# partybooth.net
KiCad netlist of a schematic drawn in EAGLE
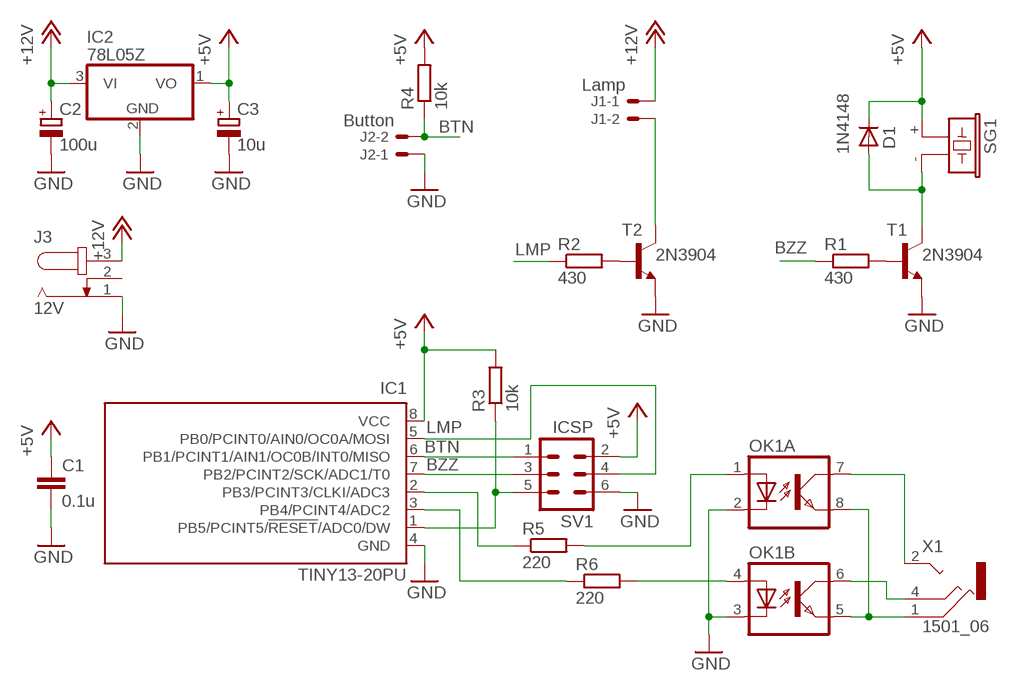
[diagram p0: schematic, sheet 1]

(export (version "E")
  (design (tool "Eeschema 10.0.6"))
  (components
    (comp (ref "C1")
      (value "0.1u")
      (footprint "eagle-import:C050-025X075")
      (libsource (lib "eagle-import") (part "C-EU050-025X075"))
    )
    (comp (ref "C2")
      (value "100u")
      (footprint "eagle-import:B45181B")
      (libsource (lib "eagle-import") (part "CPOL-EUB45181B"))
    )
    (comp (ref "C3")
      (value "10u")
      (footprint "eagle-import:B45181B")
      (libsource (lib "eagle-import") (part "CPOL-EUB45181B"))
    )
    (comp (ref "D1")
      (value "1N4148")
      (footprint "eagle-import:DO35-7")
      (libsource (lib "eagle-import") (part "1N4148DO35-7"))
    )
    (comp (ref "IC1")
      (value "TINY13-20PU")
      (footprint "eagle-import:DIL08")
      (fields (field (name "MPN") "ATTINY13-20PU"))
      (libsource (lib "eagle-import") (part "TINY13PU-20"))
    )
    (comp (ref "IC2")
      (value "78L05Z")
      (footprint "eagle-import:TO92")
      (libsource (lib "eagle-import") (part "78ZL05"))
    )
    (comp (ref "J1")
      (value "Lamp")
      (footprint "eagle-import:6410-02")
      (libsource (lib "eagle-import") (part "22-?-0227-2021"))
    )
    (comp (ref "J2")
      (value "Button")
      (footprint "eagle-import:6410-02")
      (libsource (lib "eagle-import") (part "22-?-0227-2021"))
    )
    (comp (ref "J3")
      (value "12V")
      (footprint "eagle-import:SPC4077")
      (libsource (lib "eagle-import") (part "JACK-PLUG0"))
    )
    (comp (ref "OK1")
      (value "ILD2")
      (footprint "eagle-import:DIL08")
      (libsource (lib "eagle-import") (part "ILD2"))
    )
    (comp (ref "R1")
      (value "430")
      (footprint "eagle-import:0204_7")
      (libsource (lib "eagle-import") (part "R-EU_0204/7"))
    )
    (comp (ref "R2")
      (value "430")
      (footprint "eagle-import:0204_7")
      (libsource (lib "eagle-import") (part "R-EU_0204/7"))
    )
    (comp (ref "R3")
      (value "10k")
      (footprint "eagle-import:0204_7")
      (libsource (lib "eagle-import") (part "R-EU_0204/7"))
    )
    (comp (ref "R4")
      (value "10k")
      (footprint "eagle-import:0204_7")
      (libsource (lib "eagle-import") (part "R-EU_0204/7"))
    )
    (comp (ref "R5")
      (value "220")
      (footprint "eagle-import:0204_7")
      (libsource (lib "eagle-import") (part "R-EU_0204/7"))
    )
    (comp (ref "R6")
      (value "220")
      (footprint "eagle-import:0204_7")
      (libsource (lib "eagle-import") (part "R-EU_0204/7"))
    )
    (comp (ref "SG1")
      (value "F/CM12P")
      (footprint "eagle-import:F_CM12P")
      (libsource (lib "eagle-import") (part "F/CM12P"))
    )
    (comp (ref "SV1")
      (value "ICSP")
      (footprint "eagle-import:MA03-2")
      (libsource (lib "eagle-import") (part "MA03-2"))
    )
    (comp (ref "T1")
      (value "2N3904")
      (footprint "eagle-import:TO92")
      (libsource (lib "eagle-import") (part "2N3904"))
    )
    (comp (ref "T2")
      (value "2N3904")
      (footprint "eagle-import:TO92")
      (libsource (lib "eagle-import") (part "2N3904"))
    )
    (comp (ref "X1")
      (value "1501_06")
      (footprint "eagle-import:1501_06")
      (libsource (lib "eagle-import") (part "1501_06"))
    )
  )
  (nets
    (net (code "1") (name "+5V") (class "Default")
      (node (ref "C1") (pin "1") (pinfunction "1_1") (pintype "passive"))
      (node (ref "C3") (pin "+") (pinfunction "+_+") (pintype "passive"))
      (node (ref "D1") (pin "C") (pinfunction "C_C") (pintype "passive"))
      (node (ref "IC1") (pin "8") (pinfunction "VCC_8") (pintype "power_in"))
      (node (ref "IC2") (pin "1") (pinfunction "VO_1") (pintype "passive"))
      (node (ref "R3") (pin "2") (pinfunction "2_2") (pintype "passive"))
      (node (ref "R4") (pin "2") (pinfunction "2_2") (pintype "passive"))
      (node (ref "SG1") (pin "+") (pinfunction "1_+") (pintype "passive"))
      (node (ref "SV1") (pin "2") (pinfunction "2_2") (pintype "passive"))
    )
    (net (code "2") (name "+12V") (class "Default")
      (node (ref "C2") (pin "+") (pinfunction "+_+") (pintype "passive"))
      (node (ref "IC2") (pin "3") (pinfunction "VI_3") (pintype "input"))
      (node (ref "J1") (pin "1") (pinfunction "S_1") (pintype "passive"))
      (node (ref "J3") (pin "3") (pinfunction "3_3") (pintype "passive"))
    )
    (net (code "3") (name "/BTN") (class "Default")
      (node (ref "IC1") (pin "6") (pinfunction "PB1/PCINT1/AIN1/OC0B/INT0/MISO_6") (pintype "bidirectional"))
      (node (ref "J2") (pin "2") (pinfunction "S_2") (pintype "passive"))
      (node (ref "R4") (pin "1") (pinfunction "1_1") (pintype "passive"))
      (node (ref "SV1") (pin "1") (pinfunction "1_1") (pintype "passive"))
    )
    (net (code "4") (name "/BZZ") (class "Default")
      (node (ref "IC1") (pin "7") (pinfunction "PB2/PCINT2/SCK/ADC1/T0_7") (pintype "bidirectional"))
      (node (ref "R1") (pin "1") (pinfunction "1_1") (pintype "passive"))
      (node (ref "SV1") (pin "3") (pinfunction "3_3") (pintype "passive"))
    )
    (net (code "5") (name "/LMP") (class "Default")
      (node (ref "IC1") (pin "5") (pinfunction "PB0/PCINT0/AIN0/OC0A/MOSI_5") (pintype "bidirectional"))
      (node (ref "R2") (pin "1") (pinfunction "1_1") (pintype "passive"))
      (node (ref "SV1") (pin "4") (pinfunction "4_4") (pintype "passive"))
    )
    (net (code "6") (name "GND") (class "Default")
      (node (ref "C1") (pin "2") (pinfunction "2_2") (pintype "passive"))
      (node (ref "C2") (pin "-") (pinfunction "-_-") (pintype "passive"))
      (node (ref "C3") (pin "-") (pinfunction "-_-") (pintype "passive"))
      (node (ref "IC1") (pin "4") (pinfunction "GND_4") (pintype "power_in"))
      (node (ref "IC2") (pin "2") (pinfunction "GND_2") (pintype "passive"))
      (node (ref "J2") (pin "1") (pinfunction "S_1") (pintype "passive"))
      (node (ref "J3") (pin "1") (pinfunction "1_1") (pintype "passive"))
      (node (ref "OK1") (pin "2") (pinfunction "C_2") (pintype "passive"))
      (node (ref "OK1") (pin "3") (pinfunction "C_3") (pintype "passive"))
      (node (ref "SV1") (pin "6") (pinfunction "6_6") (pintype "passive"))
      (node (ref "T1") (pin "3") (pinfunction "E_3") (pintype "passive"))
      (node (ref "T2") (pin "3") (pinfunction "E_3") (pintype "passive"))
    )
    (net (code "7") (name "Net-(IC1-PB3{slash}PCINT3{slash}CLKI{slash}ADC3)") (class "Default")
      (node (ref "IC1") (pin "2") (pinfunction "PB3/PCINT3/CLKI/ADC3_2") (pintype "bidirectional"))
      (node (ref "R5") (pin "1") (pinfunction "1_1") (pintype "passive"))
    )
    (net (code "8") (name "Net-(IC1-PB4{slash}PCINT4{slash}ADC2)") (class "Default")
      (node (ref "IC1") (pin "3") (pinfunction "PB4/PCINT4/ADC2_3") (pintype "bidirectional"))
      (node (ref "R6") (pin "1") (pinfunction "1_1") (pintype "passive"))
    )
    (net (code "9") (name "Net-(IC1-PB5{slash}PCINT5{slash}~{RESET}{slash}ADC0{slash}DW)") (class "Default")
      (node (ref "IC1") (pin "1") (pinfunction "PB5/PCINT5/~{RESET}/ADC0/DW_1") (pintype "bidirectional"))
      (node (ref "R3") (pin "1") (pinfunction "1_1") (pintype "passive"))
      (node (ref "SV1") (pin "5") (pinfunction "5_5") (pintype "passive"))
    )
    (net (code "10") (name "Net-(J1B-S)") (class "Default")
      (node (ref "J1") (pin "2") (pinfunction "S_2") (pintype "passive"))
      (node (ref "T2") (pin "1") (pinfunction "C_1") (pintype "passive"))
    )
    (net (code "11") (name "Net-(OK1A-A)") (class "Default")
      (node (ref "OK1") (pin "1") (pinfunction "A_1") (pintype "passive"))
      (node (ref "R5") (pin "2") (pinfunction "2_2") (pintype "passive"))
    )
    (net (code "12") (name "Net-(OK1A-COL)") (class "Default")
      (node (ref "OK1") (pin "7") (pinfunction "COL_7") (pintype "passive"))
      (node (ref "X1") (pin "2") (pinfunction "2_2") (pintype "passive"))
    )
    (net (code "13") (name "Net-(OK1A-EMIT)") (class "Default")
      (node (ref "OK1") (pin "5") (pinfunction "EMIT_5") (pintype "passive"))
      (node (ref "OK1") (pin "8") (pinfunction "EMIT_8") (pintype "passive"))
      (node (ref "X1") (pin "1") (pinfunction "1_1") (pintype "passive"))
    )
    (net (code "14") (name "Net-(OK1B-A)") (class "Default")
      (node (ref "OK1") (pin "4") (pinfunction "A_4") (pintype "passive"))
      (node (ref "R6") (pin "2") (pinfunction "2_2") (pintype "passive"))
    )
    (net (code "15") (name "Net-(OK1B-COL)") (class "Default")
      (node (ref "OK1") (pin "6") (pinfunction "COL_6") (pintype "passive"))
      (node (ref "X1") (pin "4") (pinfunction "3_4") (pintype "passive"))
    )
    (net (code "16") (name "Net-(SG1-2)") (class "Default")
      (node (ref "D1") (pin "A") (pinfunction "A_A") (pintype "passive"))
      (node (ref "SG1") (pin "-") (pinfunction "2_-") (pintype "passive"))
      (node (ref "T1") (pin "1") (pinfunction "C_1") (pintype "passive"))
    )
    (net (code "17") (name "Net-(T1-B)") (class "Default")
      (node (ref "R1") (pin "2") (pinfunction "2_2") (pintype "passive"))
      (node (ref "T1") (pin "2") (pinfunction "B_2") (pintype "passive"))
    )
    (net (code "18") (name "Net-(T2-B)") (class "Default")
      (node (ref "R2") (pin "2") (pinfunction "2_2") (pintype "passive"))
      (node (ref "T2") (pin "2") (pinfunction "B_2") (pintype "passive"))
    )
    (net (code "19") (name "unconnected-(J3-Pad2)") (class "Default")
      (node (ref "J3") (pin "2") (pinfunction "2_2") (pintype "passive"))
    )
  )
)
